# 0-AltSensor.net
KiCad netlist of a schematic drawn in Altium Designer
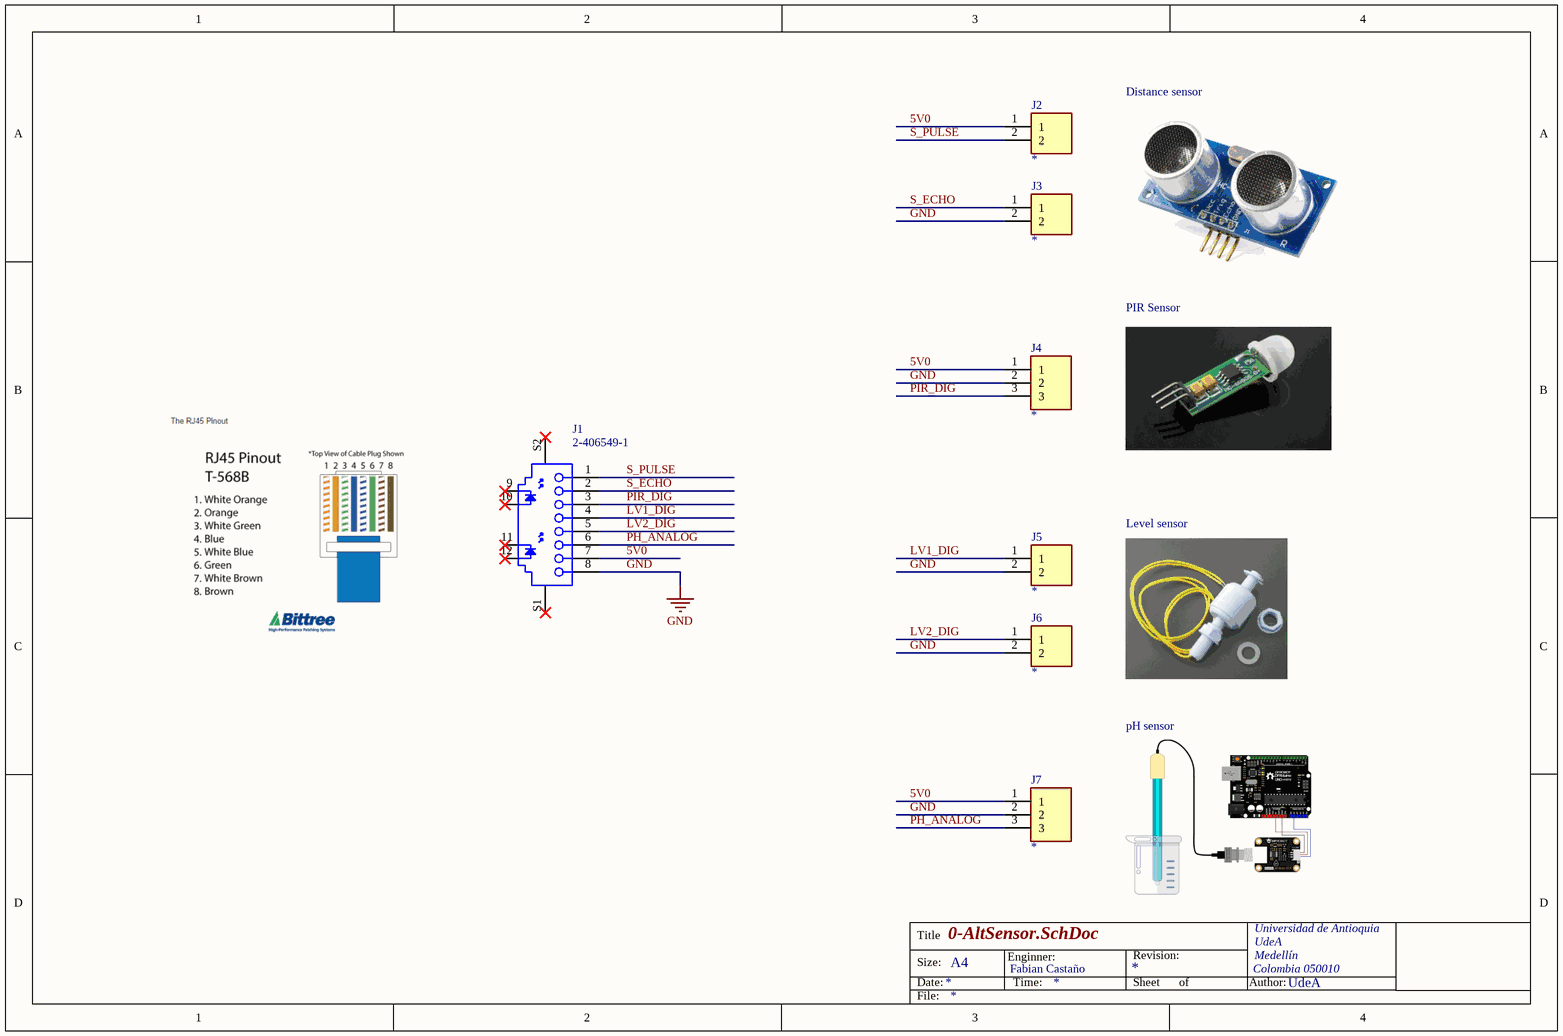
[diagram p0: 0-AltSensor.SchDoc]

(export (version "E")
  (design (tool "Eeschema 10.0.6"))
  (components
    (comp (ref "J1")
      (value "2-406549-1")
      (footprint "TECO-2-406549-1_V")
      (description "RJ45 Connector, Pitch 1.016 mm, 8 Position, Height 14.22 mm, Tail Length 3.18 mm, RoHS, Tray")
      (fields (field (name "MANUFACTURER") "TE Connectivity"))
      (libsource (lib "Altium Content Vault") (part "RJ45-12-2SHLD_A"))
    )
    (comp (ref "J2")
      (value "282841-2")
      (footprint "TE_282841-2")
      (description "Conn Terminal Block 2 POS 5.08mm Solder ST Thru-Hole 17.5A/Contact")
      (fields (field (name "MF") "TE Connectivity") (field (name "COMMENT_1") "*"))
      (libsource (lib "PTR500-2") (part "282841-2"))
    )
    (comp (ref "J3")
      (value "282841-2")
      (footprint "TE_282841-2")
      (description "Conn Terminal Block 2 POS 5.08mm Solder ST Thru-Hole 17.5A/Contact")
      (fields (field (name "MF") "TE Connectivity") (field (name "COMMENT_1") "*"))
      (libsource (lib "PTR500-2") (part "282841-2"))
    )
    (comp (ref "J4")
      (value "282841-3")
      (footprint "TE_282841-3")
      (description "Conn Terminal Block 3 POS 5.08mm Solder ST Thru-Hole 17.5A/Contact")
      (fields
        (field (name "MF") "TE Connectivity")
        (field (name "MP") "282841-2")
        (field (name "COMMENT_1") "*")
      )
      (libsource (lib "PTR500-2") (part "282841-3"))
    )
    (comp (ref "J5")
      (value "282841-2")
      (footprint "TE_282841-2")
      (description "Conn Terminal Block 2 POS 5.08mm Solder ST Thru-Hole 17.5A/Contact")
      (fields (field (name "MF") "TE Connectivity") (field (name "COMMENT_1") "*"))
      (libsource (lib "PTR500-2") (part "282841-2"))
    )
    (comp (ref "J6")
      (value "282841-2")
      (footprint "TE_282841-2")
      (description "Conn Terminal Block 2 POS 5.08mm Solder ST Thru-Hole 17.5A/Contact")
      (fields (field (name "MF") "TE Connectivity") (field (name "COMMENT_1") "*"))
      (libsource (lib "PTR500-2") (part "282841-2"))
    )
    (comp (ref "J7")
      (value "282841-3")
      (footprint "TE_282841-3")
      (description "Conn Terminal Block 3 POS 5.08mm Solder ST Thru-Hole 17.5A/Contact")
      (fields
        (field (name "MF") "TE Connectivity")
        (field (name "MP") "282841-2")
        (field (name "COMMENT_1") "*")
      )
      (libsource (lib "PTR500-2") (part "282841-3"))
    )
  )
  (nets
    (net (code "1") (name "/5V0") (class "Default")
      (node (ref "J1") (pin "7") (pinfunction "7_7") (pintype "passive"))
      (node (ref "J2") (pin "1") (pinfunction "1_1") (pintype "passive"))
      (node (ref "J4") (pin "1") (pinfunction "1_1") (pintype "passive"))
      (node (ref "J7") (pin "1") (pinfunction "1_1") (pintype "passive"))
    )
    (net (code "2") (name "/LV1_DIG") (class "Default")
      (node (ref "J1") (pin "4") (pinfunction "4_4") (pintype "passive"))
      (node (ref "J5") (pin "1") (pinfunction "1_1") (pintype "passive"))
    )
    (net (code "3") (name "/LV2_DIG") (class "Default")
      (node (ref "J1") (pin "5") (pinfunction "5_5") (pintype "passive"))
      (node (ref "J6") (pin "1") (pinfunction "1_1") (pintype "passive"))
    )
    (net (code "4") (name "/PH_ANALOG") (class "Default")
      (node (ref "J1") (pin "6") (pinfunction "6_6") (pintype "passive"))
      (node (ref "J7") (pin "3") (pinfunction "3_3") (pintype "passive"))
    )
    (net (code "5") (name "/PIR_DIG") (class "Default")
      (node (ref "J1") (pin "3") (pinfunction "3_3") (pintype "passive"))
      (node (ref "J4") (pin "3") (pinfunction "3_3") (pintype "passive"))
    )
    (net (code "6") (name "/S_ECHO") (class "Default")
      (node (ref "J1") (pin "2") (pinfunction "2_2") (pintype "passive"))
      (node (ref "J3") (pin "1") (pinfunction "1_1") (pintype "passive"))
    )
    (net (code "7") (name "/S_PULSE") (class "Default")
      (node (ref "J1") (pin "1") (pinfunction "1_1") (pintype "passive"))
      (node (ref "J2") (pin "2") (pinfunction "2_2") (pintype "passive"))
    )
    (net (code "8") (name "GND") (class "Default")
      (node (ref "J1") (pin "8") (pinfunction "8_8") (pintype "passive"))
      (node (ref "J3") (pin "2") (pinfunction "2_2") (pintype "passive"))
      (node (ref "J4") (pin "2") (pinfunction "2_2") (pintype "passive"))
      (node (ref "J5") (pin "2") (pinfunction "2_2") (pintype "passive"))
      (node (ref "J6") (pin "2") (pinfunction "2_2") (pintype "passive"))
      (node (ref "J7") (pin "2") (pinfunction "2_2") (pintype "passive"))
    )
    (net (code "9") (name "unconnected-(J1-Pad9)") (class "Default")
      (node (ref "J1") (pin "9") (pinfunction "9_9") (pintype "passive+no_connect"))
    )
    (net (code "10") (name "unconnected-(J1-Pad10)") (class "Default")
      (node (ref "J1") (pin "10") (pinfunction "10_10") (pintype "passive+no_connect"))
    )
    (net (code "11") (name "unconnected-(J1-Pad11)") (class "Default")
      (node (ref "J1") (pin "11") (pinfunction "11_11") (pintype "passive+no_connect"))
    )
    (net (code "12") (name "unconnected-(J1-Pad12)") (class "Default")
      (node (ref "J1") (pin "12") (pinfunction "12_12") (pintype "passive+no_connect"))
    )
    (net (code "13") (name "unconnected-(J1-PadS1)") (class "Default")
      (node (ref "J1") (pin "S1") (pinfunction "S1_S1") (pintype "passive+no_connect"))
    )
    (net (code "14") (name "unconnected-(J1-PadS2)") (class "Default")
      (node (ref "J1") (pin "S2") (pinfunction "S2_S2") (pintype "passive+no_connect"))
    )
  )
)
